# Sheet1.net
KiCad netlist of a schematic drawn in Altium Designer
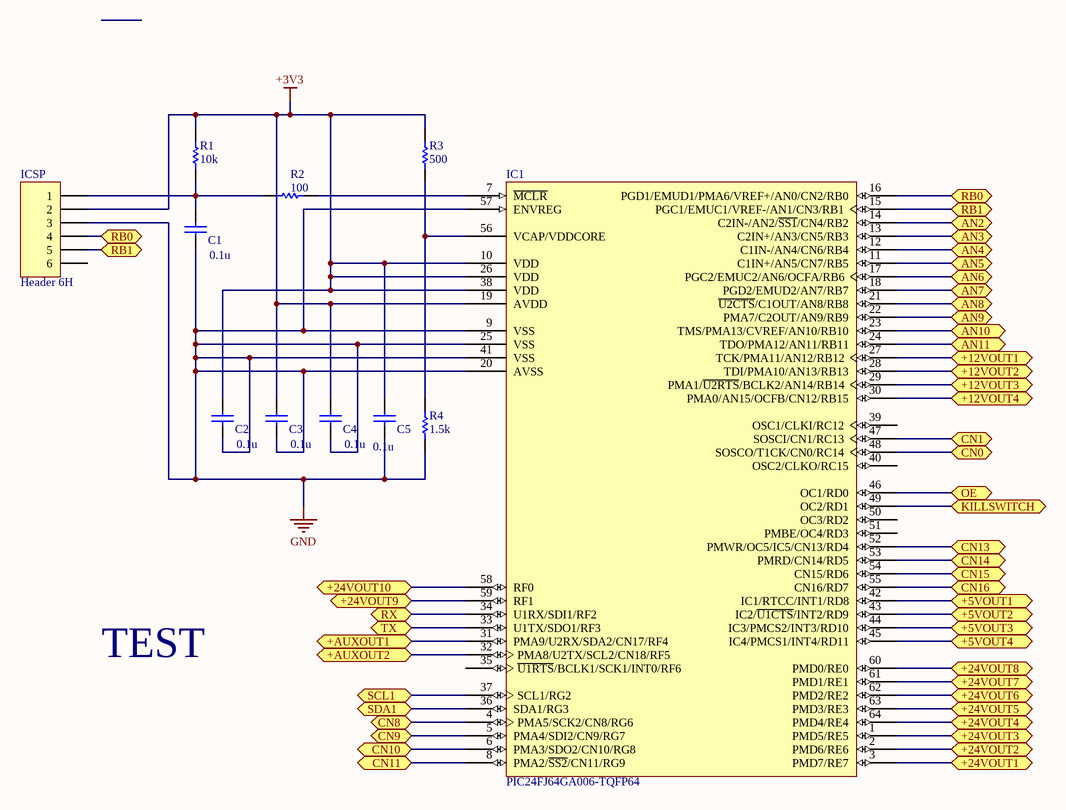
[diagram p0: Sheet1.SchDoc]

(export (version "E")
  (design (tool "Eeschema 10.0.6"))
  (components
    (comp (ref "C1")
      (value "CAP")
      (fields (field (name "ALTIUM_UNNAMED_1") "0.1u"))
      (libsource (lib "16 V¦VisibleOnAddParamList=") (part "CAP"))
    )
    (comp (ref "C2")
      (value "CAP")
      (fields (field (name "ALTIUM_UNNAMED_1") "0.1u"))
      (libsource (lib "16 V¦VisibleOnAddParamList=") (part "CAP"))
    )
    (comp (ref "C3")
      (value "CAP")
      (fields (field (name "ALTIUM_UNNAMED_1") "0.1u"))
      (libsource (lib "16 V¦VisibleOnAddParamList=") (part "CAP"))
    )
    (comp (ref "C4")
      (value "CAP")
      (fields (field (name "ALTIUM_UNNAMED_1") "0.1u"))
      (libsource (lib "16 V¦VisibleOnAddParamList=") (part "CAP"))
    )
    (comp (ref "C5")
      (value "CAP")
      (fields (field (name "ALTIUM_UNNAMED_1") "0.1u"))
      (libsource (lib "16 V¦VisibleOnAddParamList=") (part "CAP"))
    )
    (comp (ref "IC1")
      (value "PIC24FJ64GA006-TQFP64")
      (libsource (lib "PIC24F¦VisibleOnAddParamList=") (part "MC-16B-64GA006-TQFP64"))
    )
    (comp (ref "ICSP")
      (value "Header 6H")
      (footprint "HDR1X6H")
      (description "Header, 6-Pin, Right Angle")
      (fields (field (name "PUBLISHER") "Altium Limited"))
      (libsource (lib "Miscellaneous Connectors") (part "Header 6H"))
    )
    (comp (ref "R1")
      (value "RES")
      (fields (field (name "ALTIUM_UNNAMED_1") "10k"))
      (libsource (lib "0805 (2012 Metric)¦VisibleOnAddParamList=") (part "RES"))
    )
    (comp (ref "R2")
      (value "RES")
      (fields (field (name "ALTIUM_UNNAMED_1") "100"))
      (libsource (lib "0805 (2012 Metric)¦VisibleOnAddParamList=") (part "RES"))
    )
    (comp (ref "R3")
      (value "RES")
      (fields (field (name "ALTIUM_UNNAMED_1") "500"))
      (libsource (lib "0805 (2012 Metric)¦VisibleOnAddParamList=") (part "RES"))
    )
    (comp (ref "R4")
      (value "RES")
      (fields (field (name "ALTIUM_UNNAMED_1") "1.5k"))
      (libsource (lib "0805 (2012 Metric)¦VisibleOnAddParamList=") (part "RES"))
    )
  )
  (nets
    (net (code "1") (name "+3V3") (class "Default")
      (node (ref "C2") (pin "2") (pinfunction "2_2") (pintype "passive"))
      (node (ref "C3") (pin "2") (pinfunction "2_2") (pintype "passive"))
      (node (ref "C4") (pin "2") (pinfunction "2_2") (pintype "passive"))
      (node (ref "C5") (pin "2") (pinfunction "2_2") (pintype "passive"))
      (node (ref "IC1") (pin "10") (pinfunction "VDD_10") (pintype "power_in"))
      (node (ref "IC1") (pin "19") (pinfunction "AVDD_19") (pintype "power_in"))
      (node (ref "IC1") (pin "26") (pinfunction "VDD_26") (pintype "power_in"))
      (node (ref "IC1") (pin "38") (pinfunction "VDD_38") (pintype "power_in"))
      (node (ref "ICSP") (pin "2") (pinfunction "2_2") (pintype "passive"))
      (node (ref "R1") (pin "2") (pinfunction "2_2") (pintype "passive"))
      (node (ref "R3") (pin "2") (pinfunction "2_2") (pintype "passive"))
    )
    (net (code "2") (name "/+5VOUT1") (class "Default")
      (node (ref "IC1") (pin "42") (pinfunction "IC1/RTCC/INT1/RD8_42") (pintype "bidirectional"))
    )
    (net (code "3") (name "/+5VOUT2") (class "Default")
      (node (ref "IC1") (pin "43") (pinfunction "IC2/~{U1CTS}/INT2/RD9_43") (pintype "bidirectional"))
    )
    (net (code "4") (name "/+5VOUT3") (class "Default")
      (node (ref "IC1") (pin "44") (pinfunction "IC3/PMCS2/INT3/RD10_44") (pintype "bidirectional"))
    )
    (net (code "5") (name "/+5VOUT4") (class "Default")
      (node (ref "IC1") (pin "45") (pinfunction "IC4/PMCS1/INT4/RD11_45") (pintype "bidirectional"))
    )
    (net (code "6") (name "/+12VOUT1") (class "Default")
      (node (ref "IC1") (pin "27") (pinfunction "TCK/PMA11/AN12/RB12_27") (pintype "bidirectional"))
    )
    (net (code "7") (name "/+12VOUT2") (class "Default")
      (node (ref "IC1") (pin "28") (pinfunction "TDI/PMA10/AN13/RB13_28") (pintype "bidirectional"))
    )
    (net (code "8") (name "/+12VOUT3") (class "Default")
      (node (ref "IC1") (pin "29") (pinfunction "PMA1/~{U2RTS}/BCLK2/AN14/RB14_29") (pintype "bidirectional"))
    )
    (net (code "9") (name "/+12VOUT4") (class "Default")
      (node (ref "IC1") (pin "30") (pinfunction "PMA0/AN15/OCFB/CN12/RB15_30") (pintype "bidirectional"))
    )
    (net (code "10") (name "/+24VOUT1") (class "Default")
      (node (ref "IC1") (pin "3") (pinfunction "PMD7/RE7_3") (pintype "bidirectional"))
    )
    (net (code "11") (name "/+24VOUT2") (class "Default")
      (node (ref "IC1") (pin "2") (pinfunction "PMD6/RE6_2") (pintype "bidirectional"))
    )
    (net (code "12") (name "/+24VOUT3") (class "Default")
      (node (ref "IC1") (pin "1") (pinfunction "PMD5/RE5_1") (pintype "bidirectional"))
    )
    (net (code "13") (name "/+24VOUT4") (class "Default")
      (node (ref "IC1") (pin "64") (pinfunction "PMD4/RE4_64") (pintype "bidirectional"))
    )
    (net (code "14") (name "/+24VOUT5") (class "Default")
      (node (ref "IC1") (pin "63") (pinfunction "PMD3/RE3_63") (pintype "bidirectional"))
    )
    (net (code "15") (name "/+24VOUT6") (class "Default")
      (node (ref "IC1") (pin "62") (pinfunction "PMD2/RE2_62") (pintype "bidirectional"))
    )
    (net (code "16") (name "/+24VOUT7") (class "Default")
      (node (ref "IC1") (pin "61") (pinfunction "PMD1/RE1_61") (pintype "bidirectional"))
    )
    (net (code "17") (name "/+24VOUT8") (class "Default")
      (node (ref "IC1") (pin "60") (pinfunction "PMD0/RE0_60") (pintype "bidirectional"))
    )
    (net (code "18") (name "/+24VOUT9") (class "Default")
      (node (ref "IC1") (pin "59") (pinfunction "RF1_59") (pintype "bidirectional"))
    )
    (net (code "19") (name "/+24VOUT10") (class "Default")
      (node (ref "IC1") (pin "58") (pinfunction "RF0_58") (pintype "bidirectional"))
    )
    (net (code "20") (name "/+AUXOUT1") (class "Default")
      (node (ref "IC1") (pin "31") (pinfunction "PMA9/U2RX/SDA2/CN17/RF4_31") (pintype "bidirectional"))
    )
    (net (code "21") (name "/+AUXOUT2") (class "Default")
      (node (ref "IC1") (pin "32") (pinfunction "PMA8/U2TX/SCL2/CN18/RF5_32") (pintype "bidirectional"))
    )
    (net (code "22") (name "/AN2") (class "Default")
      (node (ref "IC1") (pin "14") (pinfunction "C2IN-/AN2/~{SS1}/CN4/RB2_14") (pintype "bidirectional"))
    )
    (net (code "23") (name "/AN3") (class "Default")
      (node (ref "IC1") (pin "13") (pinfunction "C2IN+/AN3/CN5/RB3_13") (pintype "bidirectional"))
    )
    (net (code "24") (name "/AN4") (class "Default")
      (node (ref "IC1") (pin "12") (pinfunction "C1IN-/AN4/CN6/RB4_12") (pintype "bidirectional"))
    )
    (net (code "25") (name "/AN5") (class "Default")
      (node (ref "IC1") (pin "11") (pinfunction "C1IN+/AN5/CN7/RB5_11") (pintype "bidirectional"))
    )
    (net (code "26") (name "/AN6") (class "Default")
      (node (ref "IC1") (pin "17") (pinfunction "PGC2/EMUC2/AN6/OCFA/RB6_17") (pintype "bidirectional"))
    )
    (net (code "27") (name "/AN7") (class "Default")
      (node (ref "IC1") (pin "18") (pinfunction "PGD2/EMUD2/AN7/RB7_18") (pintype "bidirectional"))
    )
    (net (code "28") (name "/AN8") (class "Default")
      (node (ref "IC1") (pin "21") (pinfunction "~{U2CTS}/C1OUT/AN8/RB8_21") (pintype "bidirectional"))
    )
    (net (code "29") (name "/AN9") (class "Default")
      (node (ref "IC1") (pin "22") (pinfunction "PMA7/C2OUT/AN9/RB9_22") (pintype "bidirectional"))
    )
    (net (code "30") (name "/AN10") (class "Default")
      (node (ref "IC1") (pin "23") (pinfunction "TMS/PMA13/CVREF/AN10/RB10_23") (pintype "bidirectional"))
    )
    (net (code "31") (name "/AN11") (class "Default")
      (node (ref "IC1") (pin "24") (pinfunction "TDO/PMA12/AN11/RB11_24") (pintype "bidirectional"))
    )
    (net (code "32") (name "/CN0") (class "Default")
      (node (ref "IC1") (pin "48") (pinfunction "SOSCO/T1CK/CN0/RC14_48") (pintype "bidirectional"))
    )
    (net (code "33") (name "/CN1") (class "Default")
      (node (ref "IC1") (pin "47") (pinfunction "SOSCI/CN1/RC13_47") (pintype "bidirectional"))
    )
    (net (code "34") (name "/CN8") (class "Default")
      (node (ref "IC1") (pin "4") (pinfunction "PMA5/SCK2/CN8/RG6_4") (pintype "bidirectional"))
    )
    (net (code "35") (name "/CN9") (class "Default")
      (node (ref "IC1") (pin "5") (pinfunction "PMA4/SDI2/CN9/RG7_5") (pintype "bidirectional"))
    )
    (net (code "36") (name "/CN10") (class "Default")
      (node (ref "IC1") (pin "6") (pinfunction "PMA3/SDO2/CN10/RG8_6") (pintype "bidirectional"))
    )
    (net (code "37") (name "/CN11") (class "Default")
      (node (ref "IC1") (pin "8") (pinfunction "PMA2/~{SS2}/CN11/RG9_8") (pintype "bidirectional"))
    )
    (net (code "38") (name "/CN13") (class "Default")
      (node (ref "IC1") (pin "52") (pinfunction "PMWR/OC5/IC5/CN13/RD4_52") (pintype "bidirectional"))
    )
    (net (code "39") (name "/CN14") (class "Default")
      (node (ref "IC1") (pin "53") (pinfunction "PMRD/CN14/RD5_53") (pintype "bidirectional"))
    )
    (net (code "40") (name "/CN15") (class "Default")
      (node (ref "IC1") (pin "54") (pinfunction "CN15/RD6_54") (pintype "bidirectional"))
    )
    (net (code "41") (name "/CN16") (class "Default")
      (node (ref "IC1") (pin "55") (pinfunction "CN16/RD7_55") (pintype "bidirectional"))
    )
    (net (code "42") (name "/KILLSWITCH") (class "Default")
      (node (ref "IC1") (pin "49") (pinfunction "OC2/RD1_49") (pintype "bidirectional"))
    )
    (net (code "43") (name "/OE") (class "Default")
      (node (ref "IC1") (pin "46") (pinfunction "OC1/RD0_46") (pintype "bidirectional"))
    )
    (net (code "44") (name "/RB0") (class "Default")
      (node (ref "IC1") (pin "16") (pinfunction "PGD1/EMUD1/PMA6/VREF+/AN0/CN2/RB0_16") (pintype "bidirectional"))
      (node (ref "ICSP") (pin "4") (pinfunction "4_4") (pintype "passive"))
    )
    (net (code "45") (name "/RB1") (class "Default")
      (node (ref "IC1") (pin "15") (pinfunction "PGC1/EMUC1/VREF-/AN1/CN3/RB1_15") (pintype "bidirectional"))
      (node (ref "ICSP") (pin "5") (pinfunction "5_5") (pintype "passive"))
    )
    (net (code "46") (name "/RX") (class "Default")
      (node (ref "IC1") (pin "34") (pinfunction "U1RX/SDI1/RF2_34") (pintype "bidirectional"))
    )
    (net (code "47") (name "/SCL1") (class "Default")
      (node (ref "IC1") (pin "37") (pinfunction "SCL1/RG2_37") (pintype "bidirectional"))
    )
    (net (code "48") (name "/SDA1") (class "Default")
      (node (ref "IC1") (pin "36") (pinfunction "SDA1/RG3_36") (pintype "bidirectional"))
    )
    (net (code "49") (name "/TX") (class "Default")
      (node (ref "IC1") (pin "33") (pinfunction "U1TX/SDO1/RF3_33") (pintype "bidirectional"))
    )
    (net (code "50") (name "GND") (class "Default")
      (node (ref "C1") (pin "1") (pinfunction "1_1") (pintype "passive"))
      (node (ref "C2") (pin "1") (pinfunction "1_1") (pintype "passive"))
      (node (ref "C3") (pin "1") (pinfunction "1_1") (pintype "passive"))
      (node (ref "C4") (pin "1") (pinfunction "1_1") (pintype "passive"))
      (node (ref "C5") (pin "1") (pinfunction "1_1") (pintype "passive"))
      (node (ref "IC1") (pin "20") (pinfunction "AVSS_20") (pintype "power_in"))
      (node (ref "IC1") (pin "25") (pinfunction "VSS_25") (pintype "power_in"))
      (node (ref "IC1") (pin "41") (pinfunction "VSS_41") (pintype "power_in"))
      (node (ref "IC1") (pin "57") (pinfunction "ENVREG_57") (pintype "input"))
      (node (ref "IC1") (pin "9") (pinfunction "VSS_9") (pintype "power_in"))
      (node (ref "ICSP") (pin "3") (pinfunction "3_3") (pintype "passive"))
      (node (ref "R4") (pin "1") (pinfunction "1_1") (pintype "passive"))
    )
    (net (code "51") (name "Net-(C1-Pad2)") (class "Default")
      (node (ref "C1") (pin "2") (pinfunction "2_2") (pintype "passive"))
      (node (ref "ICSP") (pin "1") (pinfunction "1_1") (pintype "passive"))
      (node (ref "R1") (pin "1") (pinfunction "1_1") (pintype "passive"))
      (node (ref "R2") (pin "1") (pinfunction "1_1") (pintype "passive"))
    )
    (net (code "52") (name "Net-(IC1-VCAP{slash}VDDCORE)") (class "Default")
      (node (ref "IC1") (pin "56") (pinfunction "VCAP/VDDCORE_56") (pintype "power_in"))
      (node (ref "R3") (pin "1") (pinfunction "1_1") (pintype "passive"))
      (node (ref "R4") (pin "2") (pinfunction "2_2") (pintype "passive"))
    )
    (net (code "53") (name "Net-(IC1-~{MCLR})") (class "Default")
      (node (ref "IC1") (pin "7") (pinfunction "~{MCLR}_7") (pintype "input"))
      (node (ref "R2") (pin "2") (pinfunction "2_2") (pintype "passive"))
    )
    (net (code "54") (name "unconnected-(IC1-OC3{slash}RD2-Pad50)") (class "Default")
      (node (ref "IC1") (pin "50") (pinfunction "OC3/RD2_50") (pintype "bidirectional"))
    )
    (net (code "55") (name "unconnected-(IC1-OSC1{slash}CLKI{slash}RC12-Pad39)") (class "Default")
      (node (ref "IC1") (pin "39") (pinfunction "OSC1/CLKI/RC12_39") (pintype "bidirectional"))
    )
    (net (code "56") (name "unconnected-(IC1-OSC2{slash}CLKO{slash}RC15-Pad40)") (class "Default")
      (node (ref "IC1") (pin "40") (pinfunction "OSC2/CLKO/RC15_40") (pintype "bidirectional"))
    )
    (net (code "57") (name "unconnected-(IC1-PMBE{slash}OC4{slash}RD3-Pad51)") (class "Default")
      (node (ref "IC1") (pin "51") (pinfunction "PMBE/OC4/RD3_51") (pintype "bidirectional"))
    )
    (net (code "58") (name "unconnected-(IC1-~{U1RTS}{slash}BCLK1{slash}SCK1{slash}INT0{slash}RF6-Pad35)") (class "Default")
      (node (ref "IC1") (pin "35") (pinfunction "~{U1RTS}/BCLK1/SCK1/INT0/RF6_35") (pintype "bidirectional"))
    )
    (net (code "59") (name "unconnected-(ICSP-Pad6)") (class "Default")
      (node (ref "ICSP") (pin "6") (pinfunction "6_6") (pintype "passive"))
    )
  )
)
